# Coil_Driver_Rev_A-PCH-2.net
KiCad netlist of a schematic drawn in Altium Designer
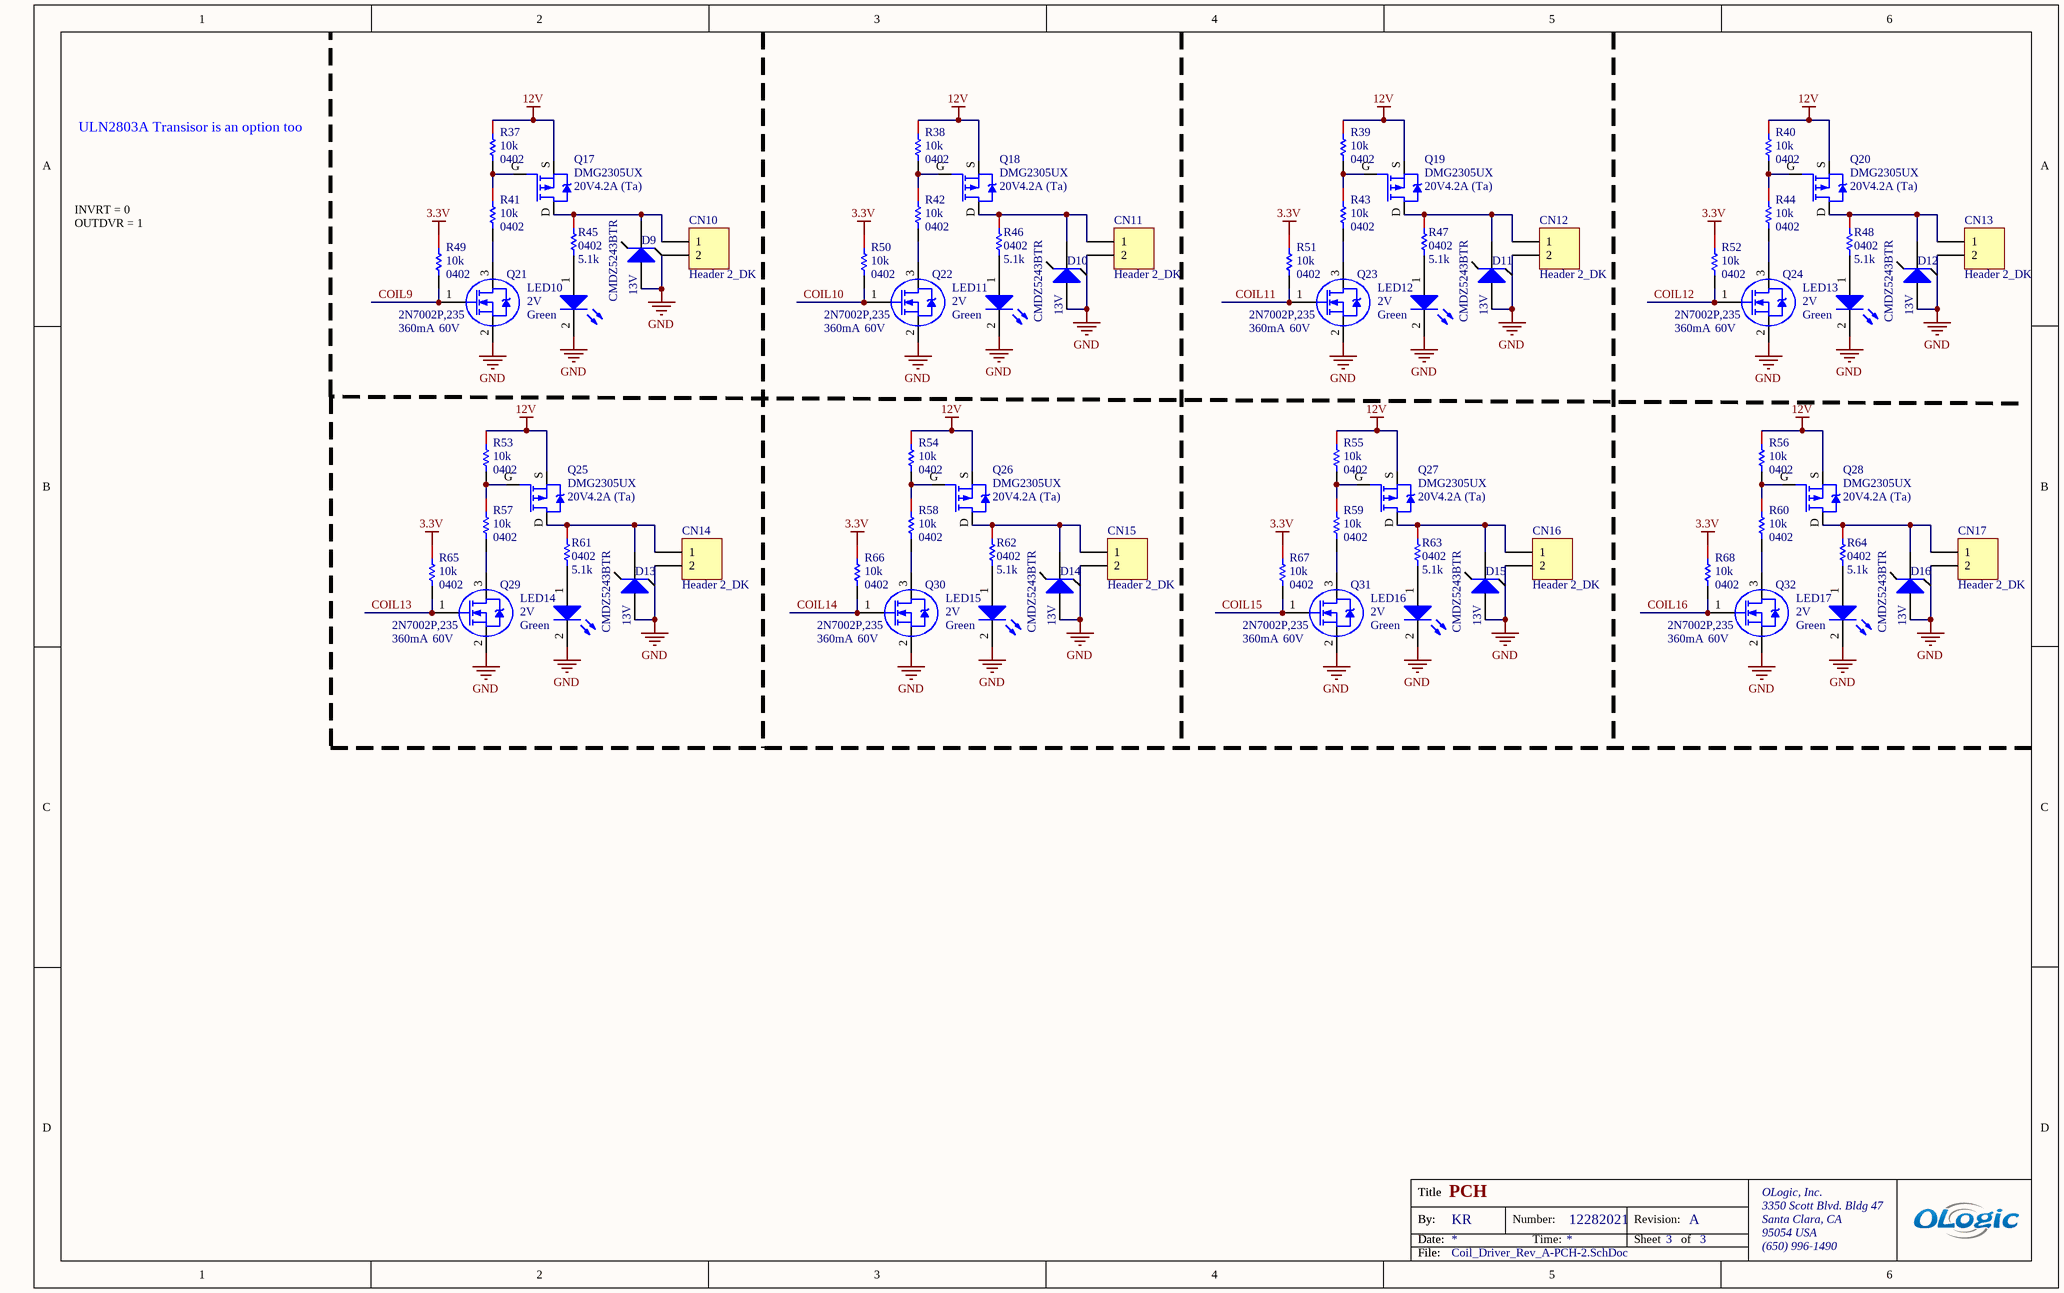
[diagram p0: Coil_Driver_Rev_A-PCH-2.SchDoc]

(export (version "E")
  (design (tool "Eeschema 10.0.6"))
  (components
    (comp (ref "CN10")
      (value "Header 2_DK")
      (footprint "HDR1X2")
      (description "Header, 2-Pin")
      (fields
        (field (name "MANUFACTURER PART NUMBER") "826936-2")
        (field (name "MANUFACTURER") "TE Connectivity AMP Connectors")
      )
      (libsource (lib "OLogic Nexus Vault") (part "Header 2_DK"))
    )
    (comp (ref "CN11")
      (value "Header 2_DK")
      (footprint "HDR1X2")
      (description "Header, 2-Pin")
      (fields
        (field (name "MANUFACTURER PART NUMBER") "826936-2")
        (field (name "MANUFACTURER") "TE Connectivity AMP Connectors")
      )
      (libsource (lib "OLogic Nexus Vault") (part "Header 2_DK"))
    )
    (comp (ref "CN12")
      (value "Header 2_DK")
      (footprint "HDR1X2")
      (description "Header, 2-Pin")
      (fields
        (field (name "MANUFACTURER PART NUMBER") "826936-2")
        (field (name "MANUFACTURER") "TE Connectivity AMP Connectors")
      )
      (libsource (lib "OLogic Nexus Vault") (part "Header 2_DK"))
    )
    (comp (ref "CN13")
      (value "Header 2_DK")
      (footprint "HDR1X2")
      (description "Header, 2-Pin")
      (fields
        (field (name "MANUFACTURER PART NUMBER") "826936-2")
        (field (name "MANUFACTURER") "TE Connectivity AMP Connectors")
      )
      (libsource (lib "OLogic Nexus Vault") (part "Header 2_DK"))
    )
    (comp (ref "CN14")
      (value "Header 2_DK")
      (footprint "HDR1X2")
      (description "Header, 2-Pin")
      (fields
        (field (name "MANUFACTURER PART NUMBER") "826936-2")
        (field (name "MANUFACTURER") "TE Connectivity AMP Connectors")
      )
      (libsource (lib "OLogic Nexus Vault") (part "Header 2_DK"))
    )
    (comp (ref "CN15")
      (value "Header 2_DK")
      (footprint "HDR1X2")
      (description "Header, 2-Pin")
      (fields
        (field (name "MANUFACTURER PART NUMBER") "826936-2")
        (field (name "MANUFACTURER") "TE Connectivity AMP Connectors")
      )
      (libsource (lib "OLogic Nexus Vault") (part "Header 2_DK"))
    )
    (comp (ref "CN16")
      (value "Header 2_DK")
      (footprint "HDR1X2")
      (description "Header, 2-Pin")
      (fields
        (field (name "MANUFACTURER PART NUMBER") "826936-2")
        (field (name "MANUFACTURER") "TE Connectivity AMP Connectors")
      )
      (libsource (lib "OLogic Nexus Vault") (part "Header 2_DK"))
    )
    (comp (ref "CN17")
      (value "Header 2_DK")
      (footprint "HDR1X2")
      (description "Header, 2-Pin")
      (fields
        (field (name "MANUFACTURER PART NUMBER") "826936-2")
        (field (name "MANUFACTURER") "TE Connectivity AMP Connectors")
      )
      (libsource (lib "OLogic Nexus Vault") (part "Header 2_DK"))
    )
    (comp (ref "D9")
      (value "CMDZ5243BTR")
      (footprint "SOD-323")
      (description "DIODE ZENER 13V 250MW SOD323")
      (fields (field (name "TOLERANCE") "5%") (field (name "ZENER VOLTAGE") "13V"))
      (libsource (lib "OLogic Nexus Vault") (part "13V 250mW"))
    )
    (comp (ref "D10")
      (value "CMDZ5243BTR")
      (footprint "SOD-323")
      (description "DIODE ZENER 13V 250MW SOD323")
      (fields (field (name "TOLERANCE") "5%") (field (name "ZENER VOLTAGE") "13V"))
      (libsource (lib "OLogic Nexus Vault") (part "13V 250mW"))
    )
    (comp (ref "D11")
      (value "CMDZ5243BTR")
      (footprint "SOD-323")
      (description "DIODE ZENER 13V 250MW SOD323")
      (fields (field (name "TOLERANCE") "5%") (field (name "ZENER VOLTAGE") "13V"))
      (libsource (lib "OLogic Nexus Vault") (part "13V 250mW"))
    )
    (comp (ref "D12")
      (value "CMDZ5243BTR")
      (footprint "SOD-323")
      (description "DIODE ZENER 13V 250MW SOD323")
      (fields (field (name "TOLERANCE") "5%") (field (name "ZENER VOLTAGE") "13V"))
      (libsource (lib "OLogic Nexus Vault") (part "13V 250mW"))
    )
    (comp (ref "D13")
      (value "CMDZ5243BTR")
      (footprint "SOD-323")
      (description "DIODE ZENER 13V 250MW SOD323")
      (fields (field (name "TOLERANCE") "5%") (field (name "ZENER VOLTAGE") "13V"))
      (libsource (lib "OLogic Nexus Vault") (part "13V 250mW"))
    )
    (comp (ref "D14")
      (value "CMDZ5243BTR")
      (footprint "SOD-323")
      (description "DIODE ZENER 13V 250MW SOD323")
      (fields (field (name "TOLERANCE") "5%") (field (name "ZENER VOLTAGE") "13V"))
      (libsource (lib "OLogic Nexus Vault") (part "13V 250mW"))
    )
    (comp (ref "D15")
      (value "CMDZ5243BTR")
      (footprint "SOD-323")
      (description "DIODE ZENER 13V 250MW SOD323")
      (fields (field (name "TOLERANCE") "5%") (field (name "ZENER VOLTAGE") "13V"))
      (libsource (lib "OLogic Nexus Vault") (part "13V 250mW"))
    )
    (comp (ref "D16")
      (value "CMDZ5243BTR")
      (footprint "SOD-323")
      (description "DIODE ZENER 13V 250MW SOD323")
      (fields (field (name "TOLERANCE") "5%") (field (name "ZENER VOLTAGE") "13V"))
      (libsource (lib "OLogic Nexus Vault") (part "13V 250mW"))
    )
    (comp (ref "LED10")
      (value "LTST-C191KGKT")
      (footprint "SM-LED-0603")
      (description "LED GREEN CLEAR THIN 0603 SMD")
      (fields
        (field (name "MANUFACTURER") "Lite-On Inc")
        (field (name "VOLTAGE - FORWARD (VF) (TYP)") "2V")
        (field (name "COLOR") "Green")
      )
      (libsource (lib "OLogic Nexus Vault") (part "OL_LED"))
    )
    (comp (ref "LED11")
      (value "LTST-C191KGKT")
      (footprint "SM-LED-0603")
      (description "LED GREEN CLEAR THIN 0603 SMD")
      (fields
        (field (name "MANUFACTURER") "Lite-On Inc")
        (field (name "VOLTAGE - FORWARD (VF) (TYP)") "2V")
        (field (name "COLOR") "Green")
      )
      (libsource (lib "OLogic Nexus Vault") (part "OL_LED"))
    )
    (comp (ref "LED12")
      (value "LTST-C191KGKT")
      (footprint "SM-LED-0603")
      (description "LED GREEN CLEAR THIN 0603 SMD")
      (fields
        (field (name "MANUFACTURER") "Lite-On Inc")
        (field (name "VOLTAGE - FORWARD (VF) (TYP)") "2V")
        (field (name "COLOR") "Green")
      )
      (libsource (lib "OLogic Nexus Vault") (part "OL_LED"))
    )
    (comp (ref "LED13")
      (value "LTST-C191KGKT")
      (footprint "SM-LED-0603")
      (description "LED GREEN CLEAR THIN 0603 SMD")
      (fields
        (field (name "MANUFACTURER") "Lite-On Inc")
        (field (name "VOLTAGE - FORWARD (VF) (TYP)") "2V")
        (field (name "COLOR") "Green")
      )
      (libsource (lib "OLogic Nexus Vault") (part "OL_LED"))
    )
    (comp (ref "LED14")
      (value "LTST-C191KGKT")
      (footprint "SM-LED-0603")
      (description "LED GREEN CLEAR THIN 0603 SMD")
      (fields
        (field (name "MANUFACTURER") "Lite-On Inc")
        (field (name "VOLTAGE - FORWARD (VF) (TYP)") "2V")
        (field (name "COLOR") "Green")
      )
      (libsource (lib "OLogic Nexus Vault") (part "OL_LED"))
    )
    (comp (ref "LED15")
      (value "LTST-C191KGKT")
      (footprint "SM-LED-0603")
      (description "LED GREEN CLEAR THIN 0603 SMD")
      (fields
        (field (name "MANUFACTURER") "Lite-On Inc")
        (field (name "VOLTAGE - FORWARD (VF) (TYP)") "2V")
        (field (name "COLOR") "Green")
      )
      (libsource (lib "OLogic Nexus Vault") (part "OL_LED"))
    )
    (comp (ref "LED16")
      (value "LTST-C191KGKT")
      (footprint "SM-LED-0603")
      (description "LED GREEN CLEAR THIN 0603 SMD")
      (fields
        (field (name "MANUFACTURER") "Lite-On Inc")
        (field (name "VOLTAGE - FORWARD (VF) (TYP)") "2V")
        (field (name "COLOR") "Green")
      )
      (libsource (lib "OLogic Nexus Vault") (part "OL_LED"))
    )
    (comp (ref "LED17")
      (value "LTST-C191KGKT")
      (footprint "SM-LED-0603")
      (description "LED GREEN CLEAR THIN 0603 SMD")
      (fields
        (field (name "MANUFACTURER") "Lite-On Inc")
        (field (name "VOLTAGE - FORWARD (VF) (TYP)") "2V")
        (field (name "COLOR") "Green")
      )
      (libsource (lib "OLogic Nexus Vault") (part "OL_LED"))
    )
    (comp (ref "Q17")
      (value "DMG2305UX")
      (footprint "DMG2305UX-7")
      (description "MOSFET P-CH 20V 4.2A SOT23")
      (fields
        (field (name "MANUFACTURER PART NUMBER") "DMG2305UX-7")
        (field (name "MANUFACTURER") "Diodes Incorporated")
        (field (name "CURRENT - CONTINUOUS DRAIN (ID) @ 25°C") "4.2A (Ta)")
        (field (name "DRAIN TO SOURCE VOLTAGE (VDSS)") "20V")
        (field (name "CREATOR") "osman")
      )
      (libsource (lib "OLogic Nexus Vault") (part "DMG2305UX"))
    )
    (comp (ref "Q18")
      (value "DMG2305UX")
      (footprint "DMG2305UX-7")
      (description "MOSFET P-CH 20V 4.2A SOT23")
      (fields
        (field (name "MANUFACTURER PART NUMBER") "DMG2305UX-7")
        (field (name "MANUFACTURER") "Diodes Incorporated")
        (field (name "CURRENT - CONTINUOUS DRAIN (ID) @ 25°C") "4.2A (Ta)")
        (field (name "DRAIN TO SOURCE VOLTAGE (VDSS)") "20V")
        (field (name "CREATOR") "osman")
      )
      (libsource (lib "OLogic Nexus Vault") (part "DMG2305UX"))
    )
    (comp (ref "Q19")
      (value "DMG2305UX")
      (footprint "DMG2305UX-7")
      (description "MOSFET P-CH 20V 4.2A SOT23")
      (fields
        (field (name "MANUFACTURER PART NUMBER") "DMG2305UX-7")
        (field (name "MANUFACTURER") "Diodes Incorporated")
        (field (name "CURRENT - CONTINUOUS DRAIN (ID) @ 25°C") "4.2A (Ta)")
        (field (name "DRAIN TO SOURCE VOLTAGE (VDSS)") "20V")
        (field (name "CREATOR") "osman")
      )
      (libsource (lib "OLogic Nexus Vault") (part "DMG2305UX"))
    )
    (comp (ref "Q20")
      (value "DMG2305UX")
      (footprint "DMG2305UX-7")
      (description "MOSFET P-CH 20V 4.2A SOT23")
      (fields
        (field (name "MANUFACTURER PART NUMBER") "DMG2305UX-7")
        (field (name "MANUFACTURER") "Diodes Incorporated")
        (field (name "CURRENT - CONTINUOUS DRAIN (ID) @ 25°C") "4.2A (Ta)")
        (field (name "DRAIN TO SOURCE VOLTAGE (VDSS)") "20V")
        (field (name "CREATOR") "osman")
      )
      (libsource (lib "OLogic Nexus Vault") (part "DMG2305UX"))
    )
    (comp (ref "Q21")
      (value "2N7002P,235")
      (footprint "SOT23-3L")
      (description "MOSFET N-CH 60V 0.36A SOT-23")
      (fields
        (field (name "CONTINUOUS DRAIN CURRENT (ID)") "360mA")
        (field (name "MANUFACTURER") "NXP Semiconductors")
        (field (name "DRAIN TO SOURCE VOLTAGE (VDSS)") "60V")
      )
      (libsource (lib "OLogic Nexus Vault") (part "2N7002P,235"))
    )
    (comp (ref "Q22")
      (value "2N7002P,235")
      (footprint "SOT23-3L")
      (description "MOSFET N-CH 60V 0.36A SOT-23")
      (fields
        (field (name "CONTINUOUS DRAIN CURRENT (ID)") "360mA")
        (field (name "MANUFACTURER") "NXP Semiconductors")
        (field (name "DRAIN TO SOURCE VOLTAGE (VDSS)") "60V")
      )
      (libsource (lib "OLogic Nexus Vault") (part "2N7002P,235"))
    )
    (comp (ref "Q23")
      (value "2N7002P,235")
      (footprint "SOT23-3L")
      (description "MOSFET N-CH 60V 0.36A SOT-23")
      (fields
        (field (name "CONTINUOUS DRAIN CURRENT (ID)") "360mA")
        (field (name "MANUFACTURER") "NXP Semiconductors")
        (field (name "DRAIN TO SOURCE VOLTAGE (VDSS)") "60V")
      )
      (libsource (lib "OLogic Nexus Vault") (part "2N7002P,235"))
    )
    (comp (ref "Q24")
      (value "2N7002P,235")
      (footprint "SOT23-3L")
      (description "MOSFET N-CH 60V 0.36A SOT-23")
      (fields
        (field (name "CONTINUOUS DRAIN CURRENT (ID)") "360mA")
        (field (name "MANUFACTURER") "NXP Semiconductors")
        (field (name "DRAIN TO SOURCE VOLTAGE (VDSS)") "60V")
      )
      (libsource (lib "OLogic Nexus Vault") (part "2N7002P,235"))
    )
    (comp (ref "Q25")
      (value "DMG2305UX")
      (footprint "DMG2305UX-7")
      (description "MOSFET P-CH 20V 4.2A SOT23")
      (fields
        (field (name "MANUFACTURER PART NUMBER") "DMG2305UX-7")
        (field (name "MANUFACTURER") "Diodes Incorporated")
        (field (name "CURRENT - CONTINUOUS DRAIN (ID) @ 25°C") "4.2A (Ta)")
        (field (name "DRAIN TO SOURCE VOLTAGE (VDSS)") "20V")
        (field (name "CREATOR") "osman")
      )
      (libsource (lib "OLogic Nexus Vault") (part "DMG2305UX"))
    )
    (comp (ref "Q26")
      (value "DMG2305UX")
      (footprint "DMG2305UX-7")
      (description "MOSFET P-CH 20V 4.2A SOT23")
      (fields
        (field (name "MANUFACTURER PART NUMBER") "DMG2305UX-7")
        (field (name "MANUFACTURER") "Diodes Incorporated")
        (field (name "CURRENT - CONTINUOUS DRAIN (ID) @ 25°C") "4.2A (Ta)")
        (field (name "DRAIN TO SOURCE VOLTAGE (VDSS)") "20V")
        (field (name "CREATOR") "osman")
      )
      (libsource (lib "OLogic Nexus Vault") (part "DMG2305UX"))
    )
    (comp (ref "Q27")
      (value "DMG2305UX")
      (footprint "DMG2305UX-7")
      (description "MOSFET P-CH 20V 4.2A SOT23")
      (fields
        (field (name "MANUFACTURER PART NUMBER") "DMG2305UX-7")
        (field (name "MANUFACTURER") "Diodes Incorporated")
        (field (name "CURRENT - CONTINUOUS DRAIN (ID) @ 25°C") "4.2A (Ta)")
        (field (name "DRAIN TO SOURCE VOLTAGE (VDSS)") "20V")
        (field (name "CREATOR") "osman")
      )
      (libsource (lib "OLogic Nexus Vault") (part "DMG2305UX"))
    )
    (comp (ref "Q28")
      (value "DMG2305UX")
      (footprint "DMG2305UX-7")
      (description "MOSFET P-CH 20V 4.2A SOT23")
      (fields
        (field (name "MANUFACTURER PART NUMBER") "DMG2305UX-7")
        (field (name "MANUFACTURER") "Diodes Incorporated")
        (field (name "CURRENT - CONTINUOUS DRAIN (ID) @ 25°C") "4.2A (Ta)")
        (field (name "DRAIN TO SOURCE VOLTAGE (VDSS)") "20V")
        (field (name "CREATOR") "osman")
      )
      (libsource (lib "OLogic Nexus Vault") (part "DMG2305UX"))
    )
    (comp (ref "Q29")
      (value "2N7002P,235")
      (footprint "SOT23-3L")
      (description "MOSFET N-CH 60V 0.36A SOT-23")
      (fields
        (field (name "CONTINUOUS DRAIN CURRENT (ID)") "360mA")
        (field (name "MANUFACTURER") "NXP Semiconductors")
        (field (name "DRAIN TO SOURCE VOLTAGE (VDSS)") "60V")
      )
      (libsource (lib "OLogic Nexus Vault") (part "2N7002P,235"))
    )
    (comp (ref "Q30")
      (value "2N7002P,235")
      (footprint "SOT23-3L")
      (description "MOSFET N-CH 60V 0.36A SOT-23")
      (fields
        (field (name "CONTINUOUS DRAIN CURRENT (ID)") "360mA")
        (field (name "MANUFACTURER") "NXP Semiconductors")
        (field (name "DRAIN TO SOURCE VOLTAGE (VDSS)") "60V")
      )
      (libsource (lib "OLogic Nexus Vault") (part "2N7002P,235"))
    )
    (comp (ref "Q31")
      (value "2N7002P,235")
      (footprint "SOT23-3L")
      (description "MOSFET N-CH 60V 0.36A SOT-23")
      (fields
        (field (name "CONTINUOUS DRAIN CURRENT (ID)") "360mA")
        (field (name "MANUFACTURER") "NXP Semiconductors")
        (field (name "DRAIN TO SOURCE VOLTAGE (VDSS)") "60V")
      )
      (libsource (lib "OLogic Nexus Vault") (part "2N7002P,235"))
    )
    (comp (ref "Q32")
      (value "2N7002P,235")
      (footprint "SOT23-3L")
      (description "MOSFET N-CH 60V 0.36A SOT-23")
      (fields
        (field (name "CONTINUOUS DRAIN CURRENT (ID)") "360mA")
        (field (name "MANUFACTURER") "NXP Semiconductors")
        (field (name "DRAIN TO SOURCE VOLTAGE (VDSS)") "60V")
      )
      (libsource (lib "OLogic Nexus Vault") (part "2N7002P,235"))
    )
    (comp (ref "R37")
      (value "RES 10K OHM 0.1% 1/16W 0402")
      (footprint "RESC0402(1005)_L")
      (description "10 kOhms ±0.1% 0.063W, 1/16W Chip Resistor 0402 (1005 Metric) Automotive AEC-Q200 Thin Film")
      (fields
        (field (name "TOLERANCE") "0.1%")
        (field (name "RESISTANCE") "10k")
        (field (name "CASE CODE (IMPERIAL)") "0402")
      )
      (libsource (lib "OLogic Nexus Vault") (part "OL_Resistor"))
    )
    (comp (ref "R38")
      (value "RES 10K OHM 0.1% 1/16W 0402")
      (footprint "RESC0402(1005)_L")
      (description "10 kOhms ±0.1% 0.063W, 1/16W Chip Resistor 0402 (1005 Metric) Automotive AEC-Q200 Thin Film")
      (fields
        (field (name "TOLERANCE") "0.1%")
        (field (name "RESISTANCE") "10k")
        (field (name "CASE CODE (IMPERIAL)") "0402")
      )
      (libsource (lib "OLogic Nexus Vault") (part "OL_Resistor"))
    )
    (comp (ref "R39")
      (value "RES 10K OHM 0.1% 1/16W 0402")
      (footprint "RESC0402(1005)_L")
      (description "10 kOhms ±0.1% 0.063W, 1/16W Chip Resistor 0402 (1005 Metric) Automotive AEC-Q200 Thin Film")
      (fields
        (field (name "TOLERANCE") "0.1%")
        (field (name "RESISTANCE") "10k")
        (field (name "CASE CODE (IMPERIAL)") "0402")
      )
      (libsource (lib "OLogic Nexus Vault") (part "OL_Resistor"))
    )
    (comp (ref "R40")
      (value "RES 10K OHM 0.1% 1/16W 0402")
      (footprint "RESC0402(1005)_L")
      (description "10 kOhms ±0.1% 0.063W, 1/16W Chip Resistor 0402 (1005 Metric) Automotive AEC-Q200 Thin Film")
      (fields
        (field (name "TOLERANCE") "0.1%")
        (field (name "RESISTANCE") "10k")
        (field (name "CASE CODE (IMPERIAL)") "0402")
      )
      (libsource (lib "OLogic Nexus Vault") (part "OL_Resistor"))
    )
    (comp (ref "R41")
      (value "RES 10K OHM 0.1% 1/16W 0402")
      (footprint "RESC0402(1005)_L")
      (description "10 kOhms ±0.1% 0.063W, 1/16W Chip Resistor 0402 (1005 Metric) Automotive AEC-Q200 Thin Film")
      (fields
        (field (name "TOLERANCE") "0.1%")
        (field (name "RESISTANCE") "10k")
        (field (name "CASE CODE (IMPERIAL)") "0402")
      )
      (libsource (lib "OLogic Nexus Vault") (part "OL_Resistor"))
    )
    (comp (ref "R42")
      (value "RES 10K OHM 0.1% 1/16W 0402")
      (footprint "RESC0402(1005)_L")
      (description "10 kOhms ±0.1% 0.063W, 1/16W Chip Resistor 0402 (1005 Metric) Automotive AEC-Q200 Thin Film")
      (fields
        (field (name "TOLERANCE") "0.1%")
        (field (name "RESISTANCE") "10k")
        (field (name "CASE CODE (IMPERIAL)") "0402")
      )
      (libsource (lib "OLogic Nexus Vault") (part "OL_Resistor"))
    )
    (comp (ref "R43")
      (value "RES 10K OHM 0.1% 1/16W 0402")
      (footprint "RESC0402(1005)_L")
      (description "10 kOhms ±0.1% 0.063W, 1/16W Chip Resistor 0402 (1005 Metric) Automotive AEC-Q200 Thin Film")
      (fields
        (field (name "TOLERANCE") "0.1%")
        (field (name "RESISTANCE") "10k")
        (field (name "CASE CODE (IMPERIAL)") "0402")
      )
      (libsource (lib "OLogic Nexus Vault") (part "OL_Resistor"))
    )
    (comp (ref "R44")
      (value "RES 10K OHM 0.1% 1/16W 0402")
      (footprint "RESC0402(1005)_L")
      (description "10 kOhms ±0.1% 0.063W, 1/16W Chip Resistor 0402 (1005 Metric) Automotive AEC-Q200 Thin Film")
      (fields
        (field (name "TOLERANCE") "0.1%")
        (field (name "RESISTANCE") "10k")
        (field (name "CASE CODE (IMPERIAL)") "0402")
      )
      (libsource (lib "OLogic Nexus Vault") (part "OL_Resistor"))
    )
    (comp (ref "R45")
      (value "5.1K")
      (footprint "RESC0402(1005)_L")
      (description "RES SMD 5.1K OHM 1% 1/10W 0402")
      (fields
        (field (name "PACKAGE (IMPERIAL)") "0402")
        (field (name "RESISTANCE") "5.1k")
        (field (name "POWER") "63mW")
        (field (name "TOLERANCE") "1%")
      )
      (libsource (lib "OLogic Nexus Vault") (part "=Resistance"))
    )
    (comp (ref "R46")
      (value "5.1K")
      (footprint "RESC0402(1005)_L")
      (description "RES SMD 5.1K OHM 1% 1/10W 0402")
      (fields
        (field (name "PACKAGE (IMPERIAL)") "0402")
        (field (name "RESISTANCE") "5.1k")
        (field (name "POWER") "63mW")
        (field (name "TOLERANCE") "1%")
      )
      (libsource (lib "OLogic Nexus Vault") (part "=Resistance"))
    )
    (comp (ref "R47")
      (value "5.1K")
      (footprint "RESC0402(1005)_L")
      (description "RES SMD 5.1K OHM 1% 1/10W 0402")
      (fields
        (field (name "PACKAGE (IMPERIAL)") "0402")
        (field (name "RESISTANCE") "5.1k")
        (field (name "POWER") "63mW")
        (field (name "TOLERANCE") "1%")
      )
      (libsource (lib "OLogic Nexus Vault") (part "=Resistance"))
    )
    (comp (ref "R48")
      (value "5.1K")
      (footprint "RESC0402(1005)_L")
      (description "RES SMD 5.1K OHM 1% 1/10W 0402")
      (fields
        (field (name "PACKAGE (IMPERIAL)") "0402")
        (field (name "RESISTANCE") "5.1k")
        (field (name "POWER") "63mW")
        (field (name "TOLERANCE") "1%")
      )
      (libsource (lib "OLogic Nexus Vault") (part "=Resistance"))
    )
    (comp (ref "R49")
      (value "RES 10K OHM 0.1% 1/16W 0402")
      (footprint "RESC0402(1005)_L")
      (description "10 kOhms ±0.1% 0.063W, 1/16W Chip Resistor 0402 (1005 Metric) Automotive AEC-Q200 Thin Film")
      (fields
        (field (name "TOLERANCE") "0.1%")
        (field (name "RESISTANCE") "10k")
        (field (name "CASE CODE (IMPERIAL)") "0402")
      )
      (libsource (lib "OLogic Nexus Vault") (part "OL_Resistor"))
    )
    (comp (ref "R50")
      (value "RES 10K OHM 0.1% 1/16W 0402")
      (footprint "RESC0402(1005)_L")
      (description "10 kOhms ±0.1% 0.063W, 1/16W Chip Resistor 0402 (1005 Metric) Automotive AEC-Q200 Thin Film")
      (fields
        (field (name "TOLERANCE") "0.1%")
        (field (name "RESISTANCE") "10k")
        (field (name "CASE CODE (IMPERIAL)") "0402")
      )
      (libsource (lib "OLogic Nexus Vault") (part "OL_Resistor"))
    )
    (comp (ref "R51")
      (value "RES 10K OHM 0.1% 1/16W 0402")
      (footprint "RESC0402(1005)_L")
      (description "10 kOhms ±0.1% 0.063W, 1/16W Chip Resistor 0402 (1005 Metric) Automotive AEC-Q200 Thin Film")
      (fields
        (field (name "TOLERANCE") "0.1%")
        (field (name "RESISTANCE") "10k")
        (field (name "CASE CODE (IMPERIAL)") "0402")
      )
      (libsource (lib "OLogic Nexus Vault") (part "OL_Resistor"))
    )
    (comp (ref "R52")
      (value "RES 10K OHM 0.1% 1/16W 0402")
      (footprint "RESC0402(1005)_L")
      (description "10 kOhms ±0.1% 0.063W, 1/16W Chip Resistor 0402 (1005 Metric) Automotive AEC-Q200 Thin Film")
      (fields
        (field (name "TOLERANCE") "0.1%")
        (field (name "RESISTANCE") "10k")
        (field (name "CASE CODE (IMPERIAL)") "0402")
      )
      (libsource (lib "OLogic Nexus Vault") (part "OL_Resistor"))
    )
    (comp (ref "R53")
      (value "RES 10K OHM 0.1% 1/16W 0402")
      (footprint "RESC0402(1005)_L")
      (description "10 kOhms ±0.1% 0.063W, 1/16W Chip Resistor 0402 (1005 Metric) Automotive AEC-Q200 Thin Film")
      (fields
        (field (name "TOLERANCE") "0.1%")
        (field (name "RESISTANCE") "10k")
        (field (name "CASE CODE (IMPERIAL)") "0402")
      )
      (libsource (lib "OLogic Nexus Vault") (part "OL_Resistor"))
    )
    (comp (ref "R54")
      (value "RES 10K OHM 0.1% 1/16W 0402")
      (footprint "RESC0402(1005)_L")
      (description "10 kOhms ±0.1% 0.063W, 1/16W Chip Resistor 0402 (1005 Metric) Automotive AEC-Q200 Thin Film")
      (fields
        (field (name "TOLERANCE") "0.1%")
        (field (name "RESISTANCE") "10k")
        (field (name "CASE CODE (IMPERIAL)") "0402")
      )
      (libsource (lib "OLogic Nexus Vault") (part "OL_Resistor"))
    )
    (comp (ref "R55")
      (value "RES 10K OHM 0.1% 1/16W 0402")
      (footprint "RESC0402(1005)_L")
      (description "10 kOhms ±0.1% 0.063W, 1/16W Chip Resistor 0402 (1005 Metric) Automotive AEC-Q200 Thin Film")
      (fields
        (field (name "TOLERANCE") "0.1%")
        (field (name "RESISTANCE") "10k")
        (field (name "CASE CODE (IMPERIAL)") "0402")
      )
      (libsource (lib "OLogic Nexus Vault") (part "OL_Resistor"))
    )
    (comp (ref "R56")
      (value "RES 10K OHM 0.1% 1/16W 0402")
      (footprint "RESC0402(1005)_L")
      (description "10 kOhms ±0.1% 0.063W, 1/16W Chip Resistor 0402 (1005 Metric) Automotive AEC-Q200 Thin Film")
      (fields
        (field (name "TOLERANCE") "0.1%")
        (field (name "RESISTANCE") "10k")
        (field (name "CASE CODE (IMPERIAL)") "0402")
      )
      (libsource (lib "OLogic Nexus Vault") (part "OL_Resistor"))
    )
    (comp (ref "R57")
      (value "RES 10K OHM 0.1% 1/16W 0402")
      (footprint "RESC0402(1005)_L")
      (description "10 kOhms ±0.1% 0.063W, 1/16W Chip Resistor 0402 (1005 Metric) Automotive AEC-Q200 Thin Film")
      (fields
        (field (name "TOLERANCE") "0.1%")
        (field (name "RESISTANCE") "10k")
        (field (name "CASE CODE (IMPERIAL)") "0402")
      )
      (libsource (lib "OLogic Nexus Vault") (part "OL_Resistor"))
    )
    (comp (ref "R58")
      (value "RES 10K OHM 0.1% 1/16W 0402")
      (footprint "RESC0402(1005)_L")
      (description "10 kOhms ±0.1% 0.063W, 1/16W Chip Resistor 0402 (1005 Metric) Automotive AEC-Q200 Thin Film")
      (fields
        (field (name "TOLERANCE") "0.1%")
        (field (name "RESISTANCE") "10k")
        (field (name "CASE CODE (IMPERIAL)") "0402")
      )
      (libsource (lib "OLogic Nexus Vault") (part "OL_Resistor"))
    )
    (comp (ref "R59")
      (value "RES 10K OHM 0.1% 1/16W 0402")
      (footprint "RESC0402(1005)_L")
      (description "10 kOhms ±0.1% 0.063W, 1/16W Chip Resistor 0402 (1005 Metric) Automotive AEC-Q200 Thin Film")
      (fields
        (field (name "TOLERANCE") "0.1%")
        (field (name "RESISTANCE") "10k")
        (field (name "CASE CODE (IMPERIAL)") "0402")
      )
      (libsource (lib "OLogic Nexus Vault") (part "OL_Resistor"))
    )
    (comp (ref "R60")
      (value "RES 10K OHM 0.1% 1/16W 0402")
      (footprint "RESC0402(1005)_L")
      (description "10 kOhms ±0.1% 0.063W, 1/16W Chip Resistor 0402 (1005 Metric) Automotive AEC-Q200 Thin Film")
      (fields
        (field (name "TOLERANCE") "0.1%")
        (field (name "RESISTANCE") "10k")
        (field (name "CASE CODE (IMPERIAL)") "0402")
      )
      (libsource (lib "OLogic Nexus Vault") (part "OL_Resistor"))
    )
    (comp (ref "R61")
      (value "5.1K")
      (footprint "RESC0402(1005)_L")
      (description "RES SMD 5.1K OHM 1% 1/10W 0402")
      (fields
        (field (name "PACKAGE (IMPERIAL)") "0402")
        (field (name "RESISTANCE") "5.1k")
        (field (name "POWER") "63mW")
        (field (name "TOLERANCE") "1%")
      )
      (libsource (lib "OLogic Nexus Vault") (part "=Resistance"))
    )
    (comp (ref "R62")
      (value "5.1K")
      (footprint "RESC0402(1005)_L")
      (description "RES SMD 5.1K OHM 1% 1/10W 0402")
      (fields
        (field (name "PACKAGE (IMPERIAL)") "0402")
        (field (name "RESISTANCE") "5.1k")
        (field (name "POWER") "63mW")
        (field (name "TOLERANCE") "1%")
      )
      (libsource (lib "OLogic Nexus Vault") (part "=Resistance"))
    )
    (comp (ref "R63")
      (value "5.1K")
      (footprint "RESC0402(1005)_L")
      (description "RES SMD 5.1K OHM 1% 1/10W 0402")
      (fields
        (field (name "PACKAGE (IMPERIAL)") "0402")
        (field (name "RESISTANCE") "5.1k")
        (field (name "POWER") "63mW")
        (field (name "TOLERANCE") "1%")
      )
      (libsource (lib "OLogic Nexus Vault") (part "=Resistance"))
    )
    (comp (ref "R64")
      (value "5.1K")
      (footprint "RESC0402(1005)_L")
      (description "RES SMD 5.1K OHM 1% 1/10W 0402")
      (fields
        (field (name "PACKAGE (IMPERIAL)") "0402")
        (field (name "RESISTANCE") "5.1k")
        (field (name "POWER") "63mW")
        (field (name "TOLERANCE") "1%")
      )
      (libsource (lib "OLogic Nexus Vault") (part "=Resistance"))
    )
    (comp (ref "R65")
      (value "RES 10K OHM 0.1% 1/16W 0402")
      (footprint "RESC0402(1005)_L")
      (description "10 kOhms ±0.1% 0.063W, 1/16W Chip Resistor 0402 (1005 Metric) Automotive AEC-Q200 Thin Film")
      (fields
        (field (name "TOLERANCE") "0.1%")
        (field (name "RESISTANCE") "10k")
        (field (name "CASE CODE (IMPERIAL)") "0402")
      )
      (libsource (lib "OLogic Nexus Vault") (part "OL_Resistor"))
    )
    (comp (ref "R66")
      (value "RES 10K OHM 0.1% 1/16W 0402")
      (footprint "RESC0402(1005)_L")
      (description "10 kOhms ±0.1% 0.063W, 1/16W Chip Resistor 0402 (1005 Metric) Automotive AEC-Q200 Thin Film")
      (fields
        (field (name "TOLERANCE") "0.1%")
        (field (name "RESISTANCE") "10k")
        (field (name "CASE CODE (IMPERIAL)") "0402")
      )
      (libsource (lib "OLogic Nexus Vault") (part "OL_Resistor"))
    )
    (comp (ref "R67")
      (value "RES 10K OHM 0.1% 1/16W 0402")
      (footprint "RESC0402(1005)_L")
      (description "10 kOhms ±0.1% 0.063W, 1/16W Chip Resistor 0402 (1005 Metric) Automotive AEC-Q200 Thin Film")
      (fields
        (field (name "TOLERANCE") "0.1%")
        (field (name "RESISTANCE") "10k")
        (field (name "CASE CODE (IMPERIAL)") "0402")
      )
      (libsource (lib "OLogic Nexus Vault") (part "OL_Resistor"))
    )
    (comp (ref "R68")
      (value "RES 10K OHM 0.1% 1/16W 0402")
      (footprint "RESC0402(1005)_L")
      (description "10 kOhms ±0.1% 0.063W, 1/16W Chip Resistor 0402 (1005 Metric) Automotive AEC-Q200 Thin Film")
      (fields
        (field (name "TOLERANCE") "0.1%")
        (field (name "RESISTANCE") "10k")
        (field (name "CASE CODE (IMPERIAL)") "0402")
      )
      (libsource (lib "OLogic Nexus Vault") (part "OL_Resistor"))
    )
  )
  (nets
    (net (code "1") (name "/COIL9") (class "Default")
      (node (ref "Q21") (pin "1") (pinfunction "G_1") (pintype "passive"))
      (node (ref "R49") (pin "2") (pinfunction "2_2") (pintype "passive"))
    )
    (net (code "2") (name "/COIL10") (class "Default")
      (node (ref "Q22") (pin "1") (pinfunction "G_1") (pintype "passive"))
      (node (ref "R50") (pin "2") (pinfunction "2_2") (pintype "passive"))
    )
    (net (code "3") (name "/COIL11") (class "Default")
      (node (ref "Q23") (pin "1") (pinfunction "G_1") (pintype "passive"))
      (node (ref "R51") (pin "2") (pinfunction "2_2") (pintype "passive"))
    )
    (net (code "4") (name "/COIL12") (class "Default")
      (node (ref "Q24") (pin "1") (pinfunction "G_1") (pintype "passive"))
      (node (ref "R52") (pin "2") (pinfunction "2_2") (pintype "passive"))
    )
    (net (code "5") (name "/COIL13") (class "Default")
      (node (ref "Q29") (pin "1") (pinfunction "G_1") (pintype "passive"))
      (node (ref "R65") (pin "2") (pinfunction "2_2") (pintype "passive"))
    )
    (net (code "6") (name "/COIL14") (class "Default")
      (node (ref "Q30") (pin "1") (pinfunction "G_1") (pintype "passive"))
      (node (ref "R66") (pin "2") (pinfunction "2_2") (pintype "passive"))
    )
    (net (code "7") (name "/COIL15") (class "Default")
      (node (ref "Q31") (pin "1") (pinfunction "G_1") (pintype "passive"))
      (node (ref "R67") (pin "2") (pinfunction "2_2") (pintype "passive"))
    )
    (net (code "8") (name "/COIL16") (class "Default")
      (node (ref "Q32") (pin "1") (pinfunction "G_1") (pintype "passive"))
      (node (ref "R68") (pin "2") (pinfunction "2_2") (pintype "passive"))
    )
    (net (code "9") (name "3.3V") (class "Default")
      (node (ref "R49") (pin "1") (pinfunction "1_1") (pintype "passive"))
      (node (ref "R50") (pin "1") (pinfunction "1_1") (pintype "passive"))
      (node (ref "R51") (pin "1") (pinfunction "1_1") (pintype "passive"))
      (node (ref "R52") (pin "1") (pinfunction "1_1") (pintype "passive"))
      (node (ref "R65") (pin "1") (pinfunction "1_1") (pintype "passive"))
      (node (ref "R66") (pin "1") (pinfunction "1_1") (pintype "passive"))
      (node (ref "R67") (pin "1") (pinfunction "1_1") (pintype "passive"))
      (node (ref "R68") (pin "1") (pinfunction "1_1") (pintype "passive"))
    )
    (net (code "10") (name "12V") (class "Default")
      (node (ref "Q17") (pin "S") (pinfunction "S_S") (pintype "passive"))
      (node (ref "Q18") (pin "S") (pinfunction "S_S") (pintype "passive"))
      (node (ref "Q19") (pin "S") (pinfunction "S_S") (pintype "passive"))
      (node (ref "Q20") (pin "S") (pinfunction "S_S") (pintype "passive"))
      (node (ref "Q25") (pin "S") (pinfunction "S_S") (pintype "passive"))
      (node (ref "Q26") (pin "S") (pinfunction "S_S") (pintype "passive"))
      (node (ref "Q27") (pin "S") (pinfunction "S_S") (pintype "passive"))
      (node (ref "Q28") (pin "S") (pinfunction "S_S") (pintype "passive"))
      (node (ref "R37") (pin "1") (pinfunction "1_1") (pintype "passive"))
      (node (ref "R38") (pin "1") (pinfunction "1_1") (pintype "passive"))
      (node (ref "R39") (pin "1") (pinfunction "1_1") (pintype "passive"))
      (node (ref "R40") (pin "1") (pinfunction "1_1") (pintype "passive"))
      (node (ref "R53") (pin "1") (pinfunction "1_1") (pintype "passive"))
      (node (ref "R54") (pin "1") (pinfunction "1_1") (pintype "passive"))
      (node (ref "R55") (pin "1") (pinfunction "1_1") (pintype "passive"))
      (node (ref "R56") (pin "1") (pinfunction "1_1") (pintype "passive"))
    )
    (net (code "11") (name "GND") (class "Default")
      (node (ref "CN10") (pin "2") (pinfunction "2_2") (pintype "passive"))
      (node (ref "CN11") (pin "2") (pinfunction "2_2") (pintype "passive"))
      (node (ref "CN12") (pin "2") (pinfunction "2_2") (pintype "passive"))
      (node (ref "CN13") (pin "2") (pinfunction "2_2") (pintype "passive"))
      (node (ref "CN14") (pin "2") (pinfunction "2_2") (pintype "passive"))
      (node (ref "CN15") (pin "2") (pinfunction "2_2") (pintype "passive"))
      (node (ref "CN16") (pin "2") (pinfunction "2_2") (pintype "passive"))
      (node (ref "CN17") (pin "2") (pinfunction "2_2") (pintype "passive"))
      (node (ref "D10") (pin "2") (pinfunction "A_2") (pintype "passive"))
      (node (ref "D11") (pin "2") (pinfunction "A_2") (pintype "passive"))
      (node (ref "D12") (pin "2") (pinfunction "A_2") (pintype "passive"))
      (node (ref "D13") (pin "2") (pinfunction "A_2") (pintype "passive"))
      (node (ref "D14") (pin "2") (pinfunction "A_2") (pintype "passive"))
      (node (ref "D15") (pin "2") (pinfunction "A_2") (pintype "passive"))
      (node (ref "D16") (pin "2") (pinfunction "A_2") (pintype "passive"))
      (node (ref "D9") (pin "2") (pinfunction "A_2") (pintype "passive"))
      (node (ref "LED10") (pin "2") (pinfunction "K_2") (pintype "passive"))
      (node (ref "LED11") (pin "2") (pinfunction "K_2") (pintype "passive"))
      (node (ref "LED12") (pin "2") (pinfunction "K_2") (pintype "passive"))
      (node (ref "LED13") (pin "2") (pinfunction "K_2") (pintype "passive"))
      (node (ref "LED14") (pin "2") (pinfunction "K_2") (pintype "passive"))
      (node (ref "LED15") (pin "2") (pinfunction "K_2") (pintype "passive"))
      (node (ref "LED16") (pin "2") (pinfunction "K_2") (pintype "passive"))
      (node (ref "LED17") (pin "2") (pinfunction "K_2") (pintype "passive"))
      (node (ref "Q21") (pin "2") (pinfunction "S_2") (pintype "passive"))
      (node (ref "Q22") (pin "2") (pinfunction "S_2") (pintype "passive"))
      (node (ref "Q23") (pin "2") (pinfunction "S_2") (pintype "passive"))
      (node (ref "Q24") (pin "2") (pinfunction "S_2") (pintype "passive"))
      (node (ref "Q29") (pin "2") (pinfunction "S_2") (pintype "passive"))
      (node (ref "Q30") (pin "2") (pinfunction "S_2") (pintype "passive"))
      (node (ref "Q31") (pin "2") (pinfunction "S_2") (pintype "passive"))
      (node (ref "Q32") (pin "2") (pinfunction "S_2") (pintype "passive"))
    )
    (net (code "12") (name "Net-(D9-K)") (class "Default")
      (node (ref "CN10") (pin "1") (pinfunction "1_1") (pintype "passive"))
      (node (ref "D9") (pin "1") (pinfunction "K_1") (pintype "passive"))
      (node (ref "Q17") (pin "D") (pinfunction "D_D") (pintype "passive"))
      (node (ref "R45") (pin "1") (pinfunction "1_1") (pintype "passive"))
    )
    (net (code "13") (name "Net-(D10-K)") (class "Default")
      (node (ref "CN11") (pin "1") (pinfunction "1_1") (pintype "passive"))
      (node (ref "D10") (pin "1") (pinfunction "K_1") (pintype "passive"))
      (node (ref "Q18") (pin "D") (pinfunction "D_D") (pintype "passive"))
      (node (ref "R46") (pin "1") (pinfunction "1_1") (pintype "passive"))
    )
    (net (code "14") (name "Net-(D11-K)") (class "Default")
      (node (ref "CN12") (pin "1") (pinfunction "1_1") (pintype "passive"))
      (node (ref "D11") (pin "1") (pinfunction "K_1") (pintype "passive"))
      (node (ref "Q19") (pin "D") (pinfunction "D_D") (pintype "passive"))
      (node (ref "R47") (pin "1") (pinfunction "1_1") (pintype "passive"))
    )
    (net (code "15") (name "Net-(D12-K)") (class "Default")
      (node (ref "CN13") (pin "1") (pinfunction "1_1") (pintype "passive"))
      (node (ref "D12") (pin "1") (pinfunction "K_1") (pintype "passive"))
      (node (ref "Q20") (pin "D") (pinfunction "D_D") (pintype "passive"))
      (node (ref "R48") (pin "1") (pinfunction "1_1") (pintype "passive"))
    )
    (net (code "16") (name "Net-(D13-K)") (class "Default")
      (node (ref "CN14") (pin "1") (pinfunction "1_1") (pintype "passive"))
      (node (ref "D13") (pin "1") (pinfunction "K_1") (pintype "passive"))
      (node (ref "Q25") (pin "D") (pinfunction "D_D") (pintype "passive"))
      (node (ref "R61") (pin "1") (pinfunction "1_1") (pintype "passive"))
    )
    (net (code "17") (name "Net-(D14-K)") (class "Default")
      (node (ref "CN15") (pin "1") (pinfunction "1_1") (pintype "passive"))
      (node (ref "D14") (pin "1") (pinfunction "K_1") (pintype "passive"))
      (node (ref "Q26") (pin "D") (pinfunction "D_D") (pintype "passive"))
      (node (ref "R62") (pin "1") (pinfunction "1_1") (pintype "passive"))
    )
    (net (code "18") (name "Net-(D15-K)") (class "Default")
      (node (ref "CN16") (pin "1") (pinfunction "1_1") (pintype "passive"))
      (node (ref "D15") (pin "1") (pinfunction "K_1") (pintype "passive"))
      (node (ref "Q27") (pin "D") (pinfunction "D_D") (pintype "passive"))
      (node (ref "R63") (pin "1") (pinfunction "1_1") (pintype "passive"))
    )
    (net (code "19") (name "Net-(D16-K)") (class "Default")
      (node (ref "CN17") (pin "1") (pinfunction "1_1") (pintype "passive"))
      (node (ref "D16") (pin "1") (pinfunction "K_1") (pintype "passive"))
      (node (ref "Q28") (pin "D") (pinfunction "D_D") (pintype "passive"))
      (node (ref "R64") (pin "1") (pinfunction "1_1") (pintype "passive"))
    )
    (net (code "20") (name "Net-(LED10-A)") (class "Default")
      (node (ref "LED10") (pin "1") (pinfunction "A_1") (pintype "passive"))
      (node (ref "R45") (pin "2") (pinfunction "2_2") (pintype "passive"))
    )
    (net (code "21") (name "Net-(LED11-A)") (class "Default")
      (node (ref "LED11") (pin "1") (pinfunction "A_1") (pintype "passive"))
      (node (ref "R46") (pin "2") (pinfunction "2_2") (pintype "passive"))
    )
    (net (code "22") (name "Net-(LED12-A)") (class "Default")
      (node (ref "LED12") (pin "1") (pinfunction "A_1") (pintype "passive"))
      (node (ref "R47") (pin "2") (pinfunction "2_2") (pintype "passive"))
    )
    (net (code "23") (name "Net-(LED13-A)") (class "Default")
      (node (ref "LED13") (pin "1") (pinfunction "A_1") (pintype "passive"))
      (node (ref "R48") (pin "2") (pinfunction "2_2") (pintype "passive"))
    )
    (net (code "24") (name "Net-(LED14-A)") (class "Default")
      (node (ref "LED14") (pin "1") (pinfunction "A_1") (pintype "passive"))
      (node (ref "R61") (pin "2") (pinfunction "2_2") (pintype "passive"))
    )
    (net (code "25") (name "Net-(LED15-A)") (class "Default")
      (node (ref "LED15") (pin "1") (pinfunction "A_1") (pintype "passive"))
      (node (ref "R62") (pin "2") (pinfunction "2_2") (pintype "passive"))
    )
    (net (code "26") (name "Net-(LED16-A)") (class "Default")
      (node (ref "LED16") (pin "1") (pinfunction "A_1") (pintype "passive"))
      (node (ref "R63") (pin "2") (pinfunction "2_2") (pintype "passive"))
    )
    (net (code "27") (name "Net-(LED17-A)") (class "Default")
      (node (ref "LED17") (pin "1") (pinfunction "A_1") (pintype "passive"))
      (node (ref "R64") (pin "2") (pinfunction "2_2") (pintype "passive"))
    )
    (net (code "28") (name "Net-(Q17-PadG)") (class "Default")
      (node (ref "Q17") (pin "G") (pinfunction "G_G") (pintype "passive"))
      (node (ref "R37") (pin "2") (pinfunction "2_2") (pintype "passive"))
      (node (ref "R41") (pin "1") (pinfunction "1_1") (pintype "passive"))
    )
    (net (code "29") (name "Net-(Q18-PadG)") (class "Default")
      (node (ref "Q18") (pin "G") (pinfunction "G_G") (pintype "passive"))
      (node (ref "R38") (pin "2") (pinfunction "2_2") (pintype "passive"))
      (node (ref "R42") (pin "1") (pinfunction "1_1") (pintype "passive"))
    )
    (net (code "30") (name "Net-(Q19-PadG)") (class "Default")
      (node (ref "Q19") (pin "G") (pinfunction "G_G") (pintype "passive"))
      (node (ref "R39") (pin "2") (pinfunction "2_2") (pintype "passive"))
      (node (ref "R43") (pin "1") (pinfunction "1_1") (pintype "passive"))
    )
    (net (code "31") (name "Net-(Q20-PadG)") (class "Default")
      (node (ref "Q20") (pin "G") (pinfunction "G_G") (pintype "passive"))
      (node (ref "R40") (pin "2") (pinfunction "2_2") (pintype "passive"))
      (node (ref "R44") (pin "1") (pinfunction "1_1") (pintype "passive"))
    )
    (net (code "32") (name "Net-(Q21-D)") (class "Default")
      (node (ref "Q21") (pin "3") (pinfunction "D_3") (pintype "passive"))
      (node (ref "R41") (pin "2") (pinfunction "2_2") (pintype "passive"))
    )
    (net (code "33") (name "Net-(Q22-D)") (class "Default")
      (node (ref "Q22") (pin "3") (pinfunction "D_3") (pintype "passive"))
      (node (ref "R42") (pin "2") (pinfunction "2_2") (pintype "passive"))
    )
    (net (code "34") (name "Net-(Q23-D)") (class "Default")
      (node (ref "Q23") (pin "3") (pinfunction "D_3") (pintype "passive"))
      (node (ref "R43") (pin "2") (pinfunction "2_2") (pintype "passive"))
    )
    (net (code "35") (name "Net-(Q24-D)") (class "Default")
      (node (ref "Q24") (pin "3") (pinfunction "D_3") (pintype "passive"))
      (node (ref "R44") (pin "2") (pinfunction "2_2") (pintype "passive"))
    )
    (net (code "36") (name "Net-(Q25-PadG)") (class "Default")
      (node (ref "Q25") (pin "G") (pinfunction "G_G") (pintype "passive"))
      (node (ref "R53") (pin "2") (pinfunction "2_2") (pintype "passive"))
      (node (ref "R57") (pin "1") (pinfunction "1_1") (pintype "passive"))
    )
    (net (code "37") (name "Net-(Q26-PadG)") (class "Default")
      (node (ref "Q26") (pin "G") (pinfunction "G_G") (pintype "passive"))
      (node (ref "R54") (pin "2") (pinfunction "2_2") (pintype "passive"))
      (node (ref "R58") (pin "1") (pinfunction "1_1") (pintype "passive"))
    )
    (net (code "38") (name "Net-(Q27-PadG)") (class "Default")
      (node (ref "Q27") (pin "G") (pinfunction "G_G") (pintype "passive"))
      (node (ref "R55") (pin "2") (pinfunction "2_2") (pintype "passive"))
      (node (ref "R59") (pin "1") (pinfunction "1_1") (pintype "passive"))
    )
    (net (code "39") (name "Net-(Q28-PadG)") (class "Default")
      (node (ref "Q28") (pin "G") (pinfunction "G_G") (pintype "passive"))
      (node (ref "R56") (pin "2") (pinfunction "2_2") (pintype "passive"))
      (node (ref "R60") (pin "1") (pinfunction "1_1") (pintype "passive"))
    )
    (net (code "40") (name "Net-(Q29-D)") (class "Default")
      (node (ref "Q29") (pin "3") (pinfunction "D_3") (pintype "passive"))
      (node (ref "R57") (pin "2") (pinfunction "2_2") (pintype "passive"))
    )
    (net (code "41") (name "Net-(Q30-D)") (class "Default")
      (node (ref "Q30") (pin "3") (pinfunction "D_3") (pintype "passive"))
      (node (ref "R58") (pin "2") (pinfunction "2_2") (pintype "passive"))
    )
    (net (code "42") (name "Net-(Q31-D)") (class "Default")
      (node (ref "Q31") (pin "3") (pinfunction "D_3") (pintype "passive"))
      (node (ref "R59") (pin "2") (pinfunction "2_2") (pintype "passive"))
    )
    (net (code "43") (name "Net-(Q32-D)") (class "Default")
      (node (ref "Q32") (pin "3") (pinfunction "D_3") (pintype "passive"))
      (node (ref "R60") (pin "2") (pinfunction "2_2") (pintype "passive"))
    )
  )
)
